# Arming.net
KiCad netlist of a schematic drawn in Altium Designer
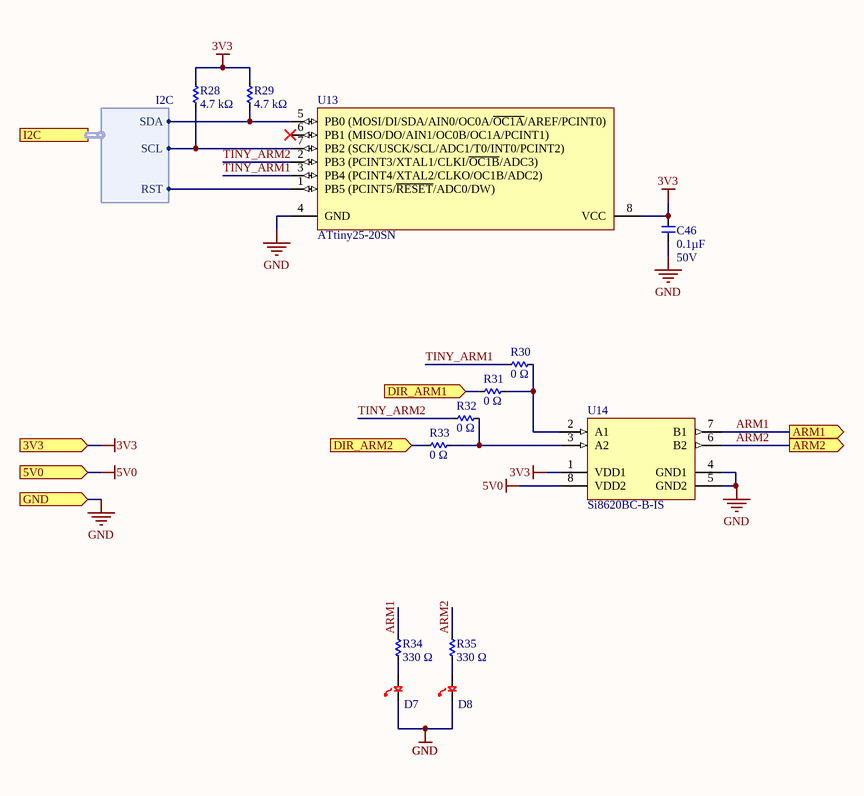
[diagram p0: Arming.SchDoc]

(export (version "E")
  (design (tool "Eeschema 10.0.6"))
  (components
    (comp (ref "C46")
      (value "__template_cap")
      (footprint "C0603")
      (description "CAP CER 0603 0.1µF X7R 50V 10%")
      (fields
        (field (name "CAPACITANCE (SHORTHAND)") "0.1µF")
        (field (name "RATED VOLTAGE") "50V")
        (field (name "MANUFACTURER") "Murata Electronics North America")
      )
      (libsource (lib "passives") (part "__template_cap"))
    )
    (comp (ref "D7")
      (value "LED_LY974")
      (footprint "0805_Diode")
      (description "LED 0805 RED 20MA")
      (fields
        (field (name "MANUFACTURER") "OSRAM Opto Semiconductors Inc")
        (field (name "MANUFACTURER PART NUMBER") "LH R974-LP-1")
      )
      (libsource (lib "SSI") (part "LED_LY974"))
    )
    (comp (ref "D8")
      (value "LED_LY974")
      (footprint "0805_Diode")
      (description "LED 0805 RED 20MA")
      (fields
        (field (name "MANUFACTURER") "OSRAM Opto Semiconductors Inc")
        (field (name "MANUFACTURER PART NUMBER") "LH R974-LP-1")
      )
      (libsource (lib "SSI") (part "LED_LY974"))
    )
    (comp (ref "R28")
      (value "__template_resistor")
      (footprint "R0603")
      (description "RES SMD 4.7K OHM 1% 1/10W 0603")
      (fields
        (field (name "RESISTANCE") "4.7 kΩ")
        (field (name "MANUFACTURER PART NUMBER") "RC0603FR-074K7L")
        (field (name "MANUFACTURER") "Yageo")
      )
      (libsource (lib "passives") (part "__template_resistor"))
    )
    (comp (ref "R29")
      (value "__template_resistor")
      (footprint "R0603")
      (description "RES SMD 4.7K OHM 1% 1/10W 0603")
      (fields
        (field (name "RESISTANCE") "4.7 kΩ")
        (field (name "MANUFACTURER PART NUMBER") "RC0603FR-074K7L")
        (field (name "MANUFACTURER") "Yageo")
      )
      (libsource (lib "passives") (part "__template_resistor"))
    )
    (comp (ref "R30")
      (value "__template_resistor")
      (footprint "R0603")
      (description "RES SMD 0 OHM JUMPER 1/10W 0603")
      (fields
        (field (name "RESISTANCE") "0 Ω")
        (field (name "MANUFACTURER PART NUMBER") "RC0603FR-070RL")
        (field (name "MANUFACTURER") "Yageo")
      )
      (libsource (lib "passives") (part "__template_resistor"))
    )
    (comp (ref "R31")
      (value "__template_resistor")
      (footprint "R0603")
      (description "RES SMD 0 OHM JUMPER 1/10W 0603")
      (fields
        (field (name "RESISTANCE") "0 Ω")
        (field (name "MANUFACTURER PART NUMBER") "RC0603FR-070RL")
        (field (name "MANUFACTURER") "Yageo")
      )
      (libsource (lib "passives") (part "__template_resistor"))
    )
    (comp (ref "R32")
      (value "__template_resistor")
      (footprint "R0603")
      (description "RES SMD 0 OHM JUMPER 1/10W 0603")
      (fields
        (field (name "RESISTANCE") "0 Ω")
        (field (name "MANUFACTURER PART NUMBER") "RC0603FR-070RL")
        (field (name "MANUFACTURER") "Yageo")
      )
      (libsource (lib "passives") (part "__template_resistor"))
    )
    (comp (ref "R33")
      (value "__template_resistor")
      (footprint "R0603")
      (description "RES SMD 0 OHM JUMPER 1/10W 0603")
      (fields
        (field (name "RESISTANCE") "0 Ω")
        (field (name "MANUFACTURER PART NUMBER") "RC0603FR-070RL")
        (field (name "MANUFACTURER") "Yageo")
      )
      (libsource (lib "passives") (part "__template_resistor"))
    )
    (comp (ref "R34")
      (value "__template_resistor")
      (footprint "R0603")
      (description "RES SMD 330 OHM 1% 1/10W 0603")
      (fields
        (field (name "RESISTANCE") "330 Ω")
        (field (name "MANUFACTURER PART NUMBER") "RC0603FR-07330RL")
        (field (name "MANUFACTURER") "Yageo")
      )
      (libsource (lib "passives") (part "__template_resistor"))
    )
    (comp (ref "R35")
      (value "__template_resistor")
      (footprint "R0603")
      (description "RES SMD 330 OHM 1% 1/10W 0603")
      (fields
        (field (name "RESISTANCE") "330 Ω")
        (field (name "MANUFACTURER PART NUMBER") "RC0603FR-07330RL")
        (field (name "MANUFACTURER") "Yageo")
      )
      (libsource (lib "passives") (part "__template_resistor"))
    )
    (comp (ref "U13")
      (value "ATtiny25-20SN")
      (footprint "8S2_N")
      (libsource (lib "Altium Content Vault") (part "MC-8B-ATT25-IL8"))
    )
    (comp (ref "U14")
      (value "Si8620BC-B-IS")
      (footprint "SLAB-SOIC-8-NB_N")
      (fields (field (name "MANUFACTURER") "Silicon Labs"))
      (libsource (lib "Altium Content Vault") (part "SLAB-Si8X20XX-SOIC-8-8"))
    )
  )
  (nets
    (net (code "2") (name "/ARM1") (class "Default")
      (node (ref "R34") (pin "2") (pintype "passive"))
      (node (ref "U14") (pin "7") (pinfunction "B1_7") (pintype "output"))
    )
    (net (code "3") (name "/ARM2") (class "Default")
      (node (ref "R35") (pin "2") (pintype "passive"))
      (node (ref "U14") (pin "6") (pinfunction "B2_6") (pintype "output"))
    )
    (net (code "4") (name "/DIR_ARM1") (class "Default") (node (ref "R31") (pin "2") (pintype "passive")))
    (net (code "5") (name "/DIR_ARM2") (class "Default") (node (ref "R33") (pin "2") (pintype "passive")))
    (net (code "6") (name "/RST") (class "Default")
      (node (ref "U13") (pin "1") (pinfunction "PB5_(PCINT5/~{RESET}/ADC0/DW)_1") (pintype "bidirectional"))
    )
    (net (code "7") (name "/SCL") (class "Default")
      (node (ref "R28") (pin "1") (pintype "passive"))
      (node (ref "U13") (pin "7") (pinfunction "PB2_(SCK/USCK/SCL/ADC1/T0/INT0/PCINT2)_7") (pintype "bidirectional"))
    )
    (net (code "8") (name "/SDA") (class "Default")
      (node (ref "R29") (pin "1") (pintype "passive"))
      (node (ref "U13") (pin "5") (pinfunction "PB0_(MOSI/DI/SDA/AIN0/OC0A/~{OC1A}/AREF/PCINT0)_5") (pintype "bidirectional"))
    )
    (net (code "9") (name "/TINY_ARM1") (class "Default")
      (node (ref "R30") (pin "2") (pintype "passive"))
      (node (ref "U13") (pin "3") (pinfunction "PB4_(PCINT4/XTAL2/CLKO/OC1B/ADC2)_3") (pintype "bidirectional"))
    )
    (net (code "10") (name "/TINY_ARM2") (class "Default")
      (node (ref "R32") (pin "2") (pintype "passive"))
      (node (ref "U13") (pin "2") (pinfunction "PB3_(PCINT3/XTAL1/CLKI/~{OC1B}/ADC3)_2") (pintype "bidirectional"))
    )
    (net (code "12") (name "3V3") (class "Default")
      (node (ref "C46") (pin "1") (pintype "passive"))
      (node (ref "R28") (pin "2") (pintype "passive"))
      (node (ref "R29") (pin "2") (pintype "passive"))
      (node (ref "U13") (pin "8") (pinfunction "VCC_8") (pintype "power_in"))
      (node (ref "U14") (pin "1") (pinfunction "VDD1_1") (pintype "power_in"))
    )
    (net (code "13") (name "5V0") (class "Default")
      (node (ref "U14") (pin "8") (pinfunction "VDD2_8") (pintype "power_in"))
    )
    (net (code "14") (name "GND") (class "Default")
      (node (ref "C46") (pin "2") (pintype "passive"))
      (node (ref "D7") (pin "1") (pintype "passive"))
      (node (ref "D8") (pin "1") (pintype "passive"))
      (node (ref "U13") (pin "4") (pinfunction "GND_4") (pintype "power_in"))
      (node (ref "U14") (pin "4") (pinfunction "GND1_4") (pintype "power_in"))
      (node (ref "U14") (pin "5") (pinfunction "GND2_5") (pintype "power_in"))
    )
    (net (code "15") (name "Net-(D7-Pad2)") (class "Default")
      (node (ref "D7") (pin "2") (pintype "passive"))
      (node (ref "R34") (pin "1") (pintype "passive"))
    )
    (net (code "16") (name "Net-(D8-Pad2)") (class "Default")
      (node (ref "D8") (pin "2") (pintype "passive"))
      (node (ref "R35") (pin "1") (pintype "passive"))
    )
    (net (code "17") (name "Net-(U14-A1)") (class "Default")
      (node (ref "R30") (pin "1") (pintype "passive"))
      (node (ref "R31") (pin "1") (pintype "passive"))
      (node (ref "U14") (pin "2") (pinfunction "A1_2") (pintype "input"))
    )
    (net (code "18") (name "Net-(U14-A2)") (class "Default")
      (node (ref "R32") (pin "1") (pintype "passive"))
      (node (ref "R33") (pin "1") (pintype "passive"))
      (node (ref "U14") (pin "3") (pinfunction "A2_3") (pintype "input"))
    )
    (net (code "19") (name "unconnected-(U13-PB1_(MISO{slash}DO{slash}AIN1{slash}OC0B{slash}OC1A{slash}PCINT1)-Pad6)") (class "Default")
      (node (ref "U13") (pin "6") (pinfunction "PB1_(MISO/DO/AIN1/OC0B/OC1A/PCINT1)_6") (pintype "bidirectional+no_connect"))
    )
  )
)
